# POWERSUPPLAY.net
KiCad netlist of a schematic drawn in EAGLE
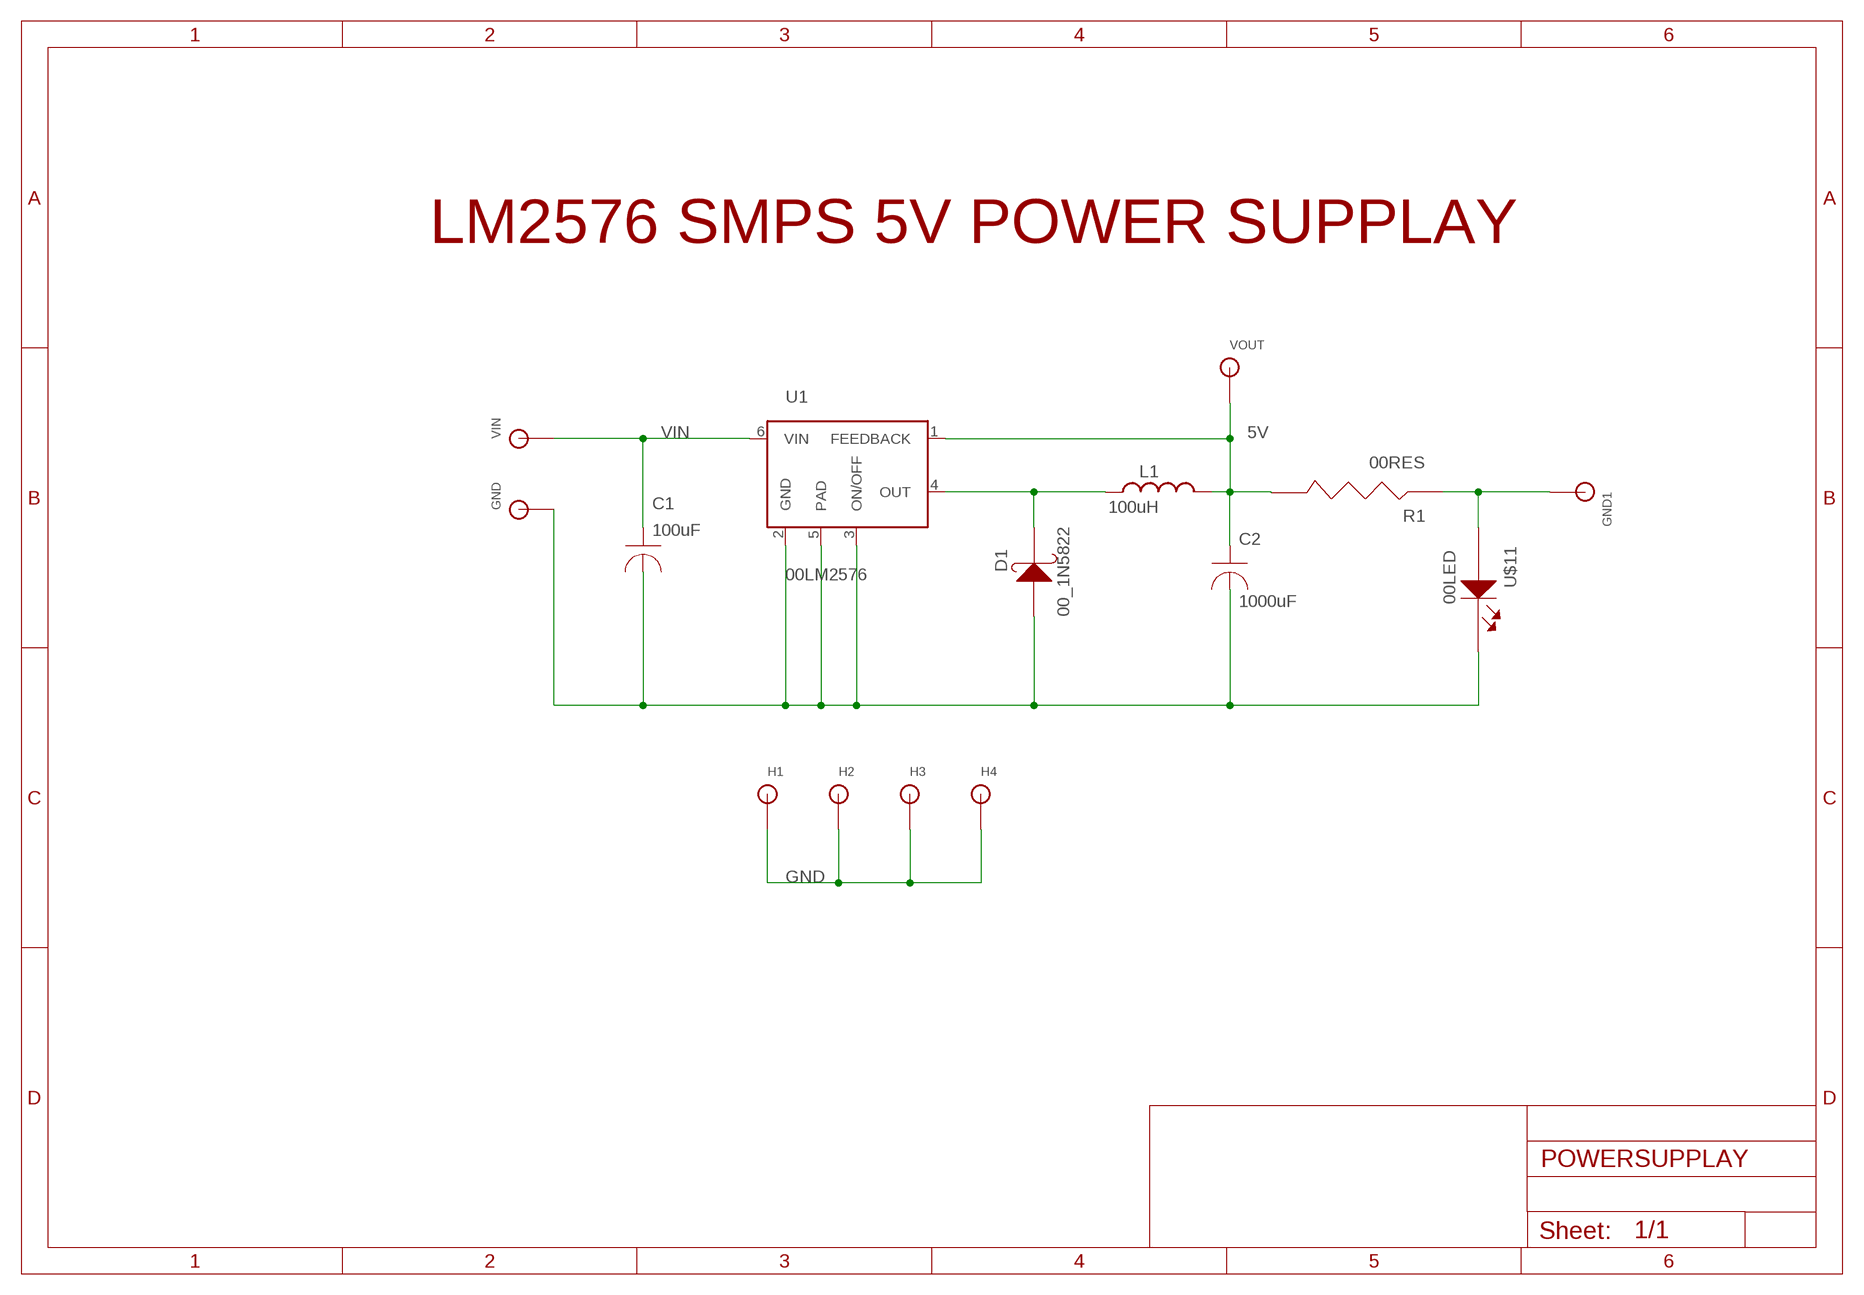
[diagram p0: schematic, sheet 1]

(export (version "E")
  (design (tool "Eeschema 10.0.6"))
  (components
    (comp (ref "C1")
      (value "100uF")
      (footprint "eagle-import:00CAP")
      (libsource (lib "eagle-import") (part "00CAP"))
    )
    (comp (ref "C2")
      (value "1000uF")
      (footprint "eagle-import:00CAP")
      (libsource (lib "eagle-import") (part "00CAP"))
    )
    (comp (ref "D1")
      (value "00_1N5822")
      (footprint "eagle-import:00_1N5822")
      (libsource (lib "eagle-import") (part "00_1N5822"))
    )
    (comp (ref "GND")
      (value "00PAD")
      (footprint "eagle-import:00PAD")
      (libsource (lib "eagle-import") (part "00PAD"))
    )
    (comp (ref "GND1")
      (value "MH_HOLE")
      (footprint "eagle-import:00PAD")
      (libsource (lib "eagle-import") (part "MH_HOLE"))
    )
    (comp (ref "H1")
      (value "MH_HOLE")
      (footprint "eagle-import:00PAD")
      (libsource (lib "eagle-import") (part "MH_HOLE"))
    )
    (comp (ref "H2")
      (value "MH_HOLE")
      (footprint "eagle-import:00PAD")
      (libsource (lib "eagle-import") (part "MH_HOLE"))
    )
    (comp (ref "H3")
      (value "MH_HOLE")
      (footprint "eagle-import:00PAD")
      (libsource (lib "eagle-import") (part "MH_HOLE"))
    )
    (comp (ref "H4")
      (value "MH_HOLE")
      (footprint "eagle-import:00PAD")
      (libsource (lib "eagle-import") (part "MH_HOLE"))
    )
    (comp (ref "L1")
      (value "100uH")
      (footprint "eagle-import:01INDUCTOR")
      (libsource (lib "eagle-import") (part "01INDUCTOR"))
    )
    (comp (ref "R1")
      (value "00RES")
      (footprint "eagle-import:00RES")
      (libsource (lib "eagle-import") (part "00RES"))
    )
    (comp (ref "U$11")
      (value "00LED")
      (footprint "eagle-import:0805_LED")
      (libsource (lib "eagle-import") (part "00LED"))
    )
    (comp (ref "U1")
      (value "00LM2576")
      (footprint "eagle-import:00LM2576")
      (libsource (lib "eagle-import") (part "00LM2576"))
    )
    (comp (ref "VIN")
      (value "00PAD")
      (footprint "eagle-import:00PAD")
      (libsource (lib "eagle-import") (part "00PAD"))
    )
    (comp (ref "VOUT")
      (value "MH_HOLE")
      (footprint "eagle-import:00PAD")
      (libsource (lib "eagle-import") (part "MH_HOLE"))
    )
  )
  (nets
    (net (code "1") (name "/5V") (class "Default")
      (node (ref "C2") (pin "1") (pinfunction "1_1") (pintype "bidirectional"))
      (node (ref "L1") (pin "2") (pinfunction "2_2") (pintype "passive"))
      (node (ref "R1") (pin "2") (pinfunction "P$2_2") (pintype "passive"))
      (node (ref "U1") (pin "1") (pinfunction "FEEDBACK_1") (pintype "passive"))
      (node (ref "VOUT") (pin "1") (pinfunction "P$1_1") (pintype "passive"))
    )
    (net (code "2") (name "/GND") (class "Default")
      (node (ref "H1") (pin "1") (pinfunction "P$1_1") (pintype "passive"))
      (node (ref "H2") (pin "1") (pinfunction "P$1_1") (pintype "passive"))
      (node (ref "H3") (pin "1") (pinfunction "P$1_1") (pintype "passive"))
      (node (ref "H4") (pin "1") (pinfunction "P$1_1") (pintype "passive"))
    )
    (net (code "3") (name "/VIN") (class "Default")
      (node (ref "C1") (pin "1") (pinfunction "1_1") (pintype "bidirectional"))
      (node (ref "U1") (pin "6") (pinfunction "VIN_6") (pintype "passive"))
      (node (ref "VIN") (pin "1") (pinfunction "P$1_1") (pintype "passive"))
    )
    (net (code "4") (name "Net-(GND-P$1)") (class "Default")
      (node (ref "C1") (pin "2") (pinfunction "2_2") (pintype "bidirectional"))
      (node (ref "C2") (pin "2") (pinfunction "2_2") (pintype "bidirectional"))
      (node (ref "D1") (pin "1") (pinfunction "1_1") (pintype "passive"))
      (node (ref "GND") (pin "1") (pinfunction "P$1_1") (pintype "passive"))
      (node (ref "U$11") (pin "2") (pinfunction "2_2") (pintype "passive"))
      (node (ref "U1") (pin "2") (pinfunction "GND_2") (pintype "passive"))
      (node (ref "U1") (pin "3") (pinfunction "ON/OFF_3") (pintype "passive"))
      (node (ref "U1") (pin "5") (pinfunction "PAD_5") (pintype "passive"))
    )
    (net (code "5") (name "Net-(GND1-P$1)") (class "Default")
      (node (ref "GND1") (pin "1") (pinfunction "P$1_1") (pintype "passive"))
      (node (ref "R1") (pin "1") (pinfunction "P$1_1") (pintype "passive"))
      (node (ref "U$11") (pin "1") (pinfunction "1_1") (pintype "passive"))
    )
    (net (code "6") (name "Net-(U1-OUT)") (class "Default")
      (node (ref "D1") (pin "2") (pinfunction "2_2") (pintype "passive"))
      (node (ref "L1") (pin "1") (pinfunction "1_1") (pintype "passive"))
      (node (ref "U1") (pin "4") (pinfunction "OUT_4") (pintype "passive"))
    )
  )
)
